# multi.net
KiCad netlist of a schematic drawn in EAGLE
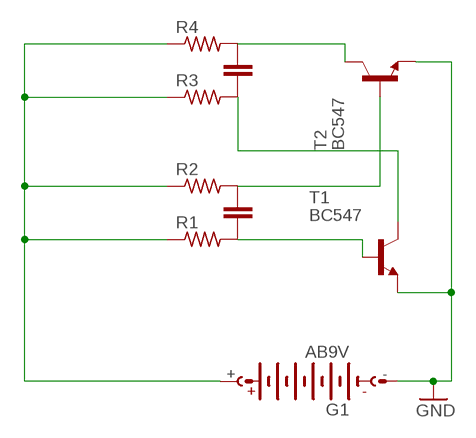
[diagram p0: schematic, sheet 1]

(export (version "E")
  (design (tool "Eeschema 10.0.6"))
  (components
    (comp (ref "G1")
      (value "AB9V")
      (footprint "eagle-import:AB9V")
      (libsource (lib "eagle-import") (part "AB9V"))
    )
    (comp (ref "R1")
      (value "R-US_R0805")
      (footprint "eagle-import:R0805")
      (libsource (lib "eagle-import") (part "R-US_R0805"))
    )
    (comp (ref "R2")
      (value "R-US_R0805")
      (footprint "eagle-import:R0805")
      (libsource (lib "eagle-import") (part "R-US_R0805"))
    )
    (comp (ref "R3")
      (value "R-US_R0805")
      (footprint "eagle-import:R0805")
      (libsource (lib "eagle-import") (part "R-US_R0805"))
    )
    (comp (ref "R4")
      (value "R-US_R0805")
      (footprint "eagle-import:R0805")
      (libsource (lib "eagle-import") (part "R-US_R0805"))
    )
    (comp (ref "T1")
      (value "BC547")
      (footprint "eagle-import:TO92")
      (libsource (lib "eagle-import") (part "BC547"))
    )
    (comp (ref "T2")
      (value "BC547")
      (footprint "eagle-import:TO92")
      (libsource (lib "eagle-import") (part "BC547"))
    )
  )
  (nets
    (net (code "1") (name "GND") (class "Default")
      (node (ref "G1") (pin "-") (pinfunction "-_-") (pintype "passive"))
      (node (ref "T1") (pin "1") (pinfunction "E_1") (pintype "passive"))
      (node (ref "T2") (pin "1") (pinfunction "E_1") (pintype "passive"))
    )
    (net (code "2") (name "Net-(G1-Pad+)") (class "Default")
      (node (ref "G1") (pin "+") (pinfunction "+_+") (pintype "passive"))
      (node (ref "R1") (pin "1") (pinfunction "1_1") (pintype "passive"))
      (node (ref "R2") (pin "1") (pinfunction "1_1") (pintype "passive"))
      (node (ref "R3") (pin "1") (pinfunction "1_1") (pintype "passive"))
      (node (ref "R4") (pin "1") (pinfunction "1_1") (pintype "passive"))
    )
    (net (code "3") (name "Net-(T1-B)") (class "Default")
      (node (ref "R1") (pin "2") (pinfunction "2_2") (pintype "passive"))
      (node (ref "T1") (pin "2") (pinfunction "B_2") (pintype "passive"))
    )
    (net (code "4") (name "Net-(T1-C)") (class "Default")
      (node (ref "R3") (pin "2") (pinfunction "2_2") (pintype "passive"))
      (node (ref "T1") (pin "3") (pinfunction "C_3") (pintype "passive"))
    )
    (net (code "5") (name "Net-(T2-B)") (class "Default")
      (node (ref "R2") (pin "2") (pinfunction "2_2") (pintype "passive"))
      (node (ref "T2") (pin "2") (pinfunction "B_2") (pintype "passive"))
    )
    (net (code "6") (name "Net-(T2-C)") (class "Default")
      (node (ref "R4") (pin "2") (pinfunction "2_2") (pintype "passive"))
      (node (ref "T2") (pin "3") (pinfunction "C_3") (pintype "passive"))
    )
  )
)
